# Adafruit_ESP32-S3_TFT_Feather.net
KiCad netlist of a schematic drawn in EAGLE
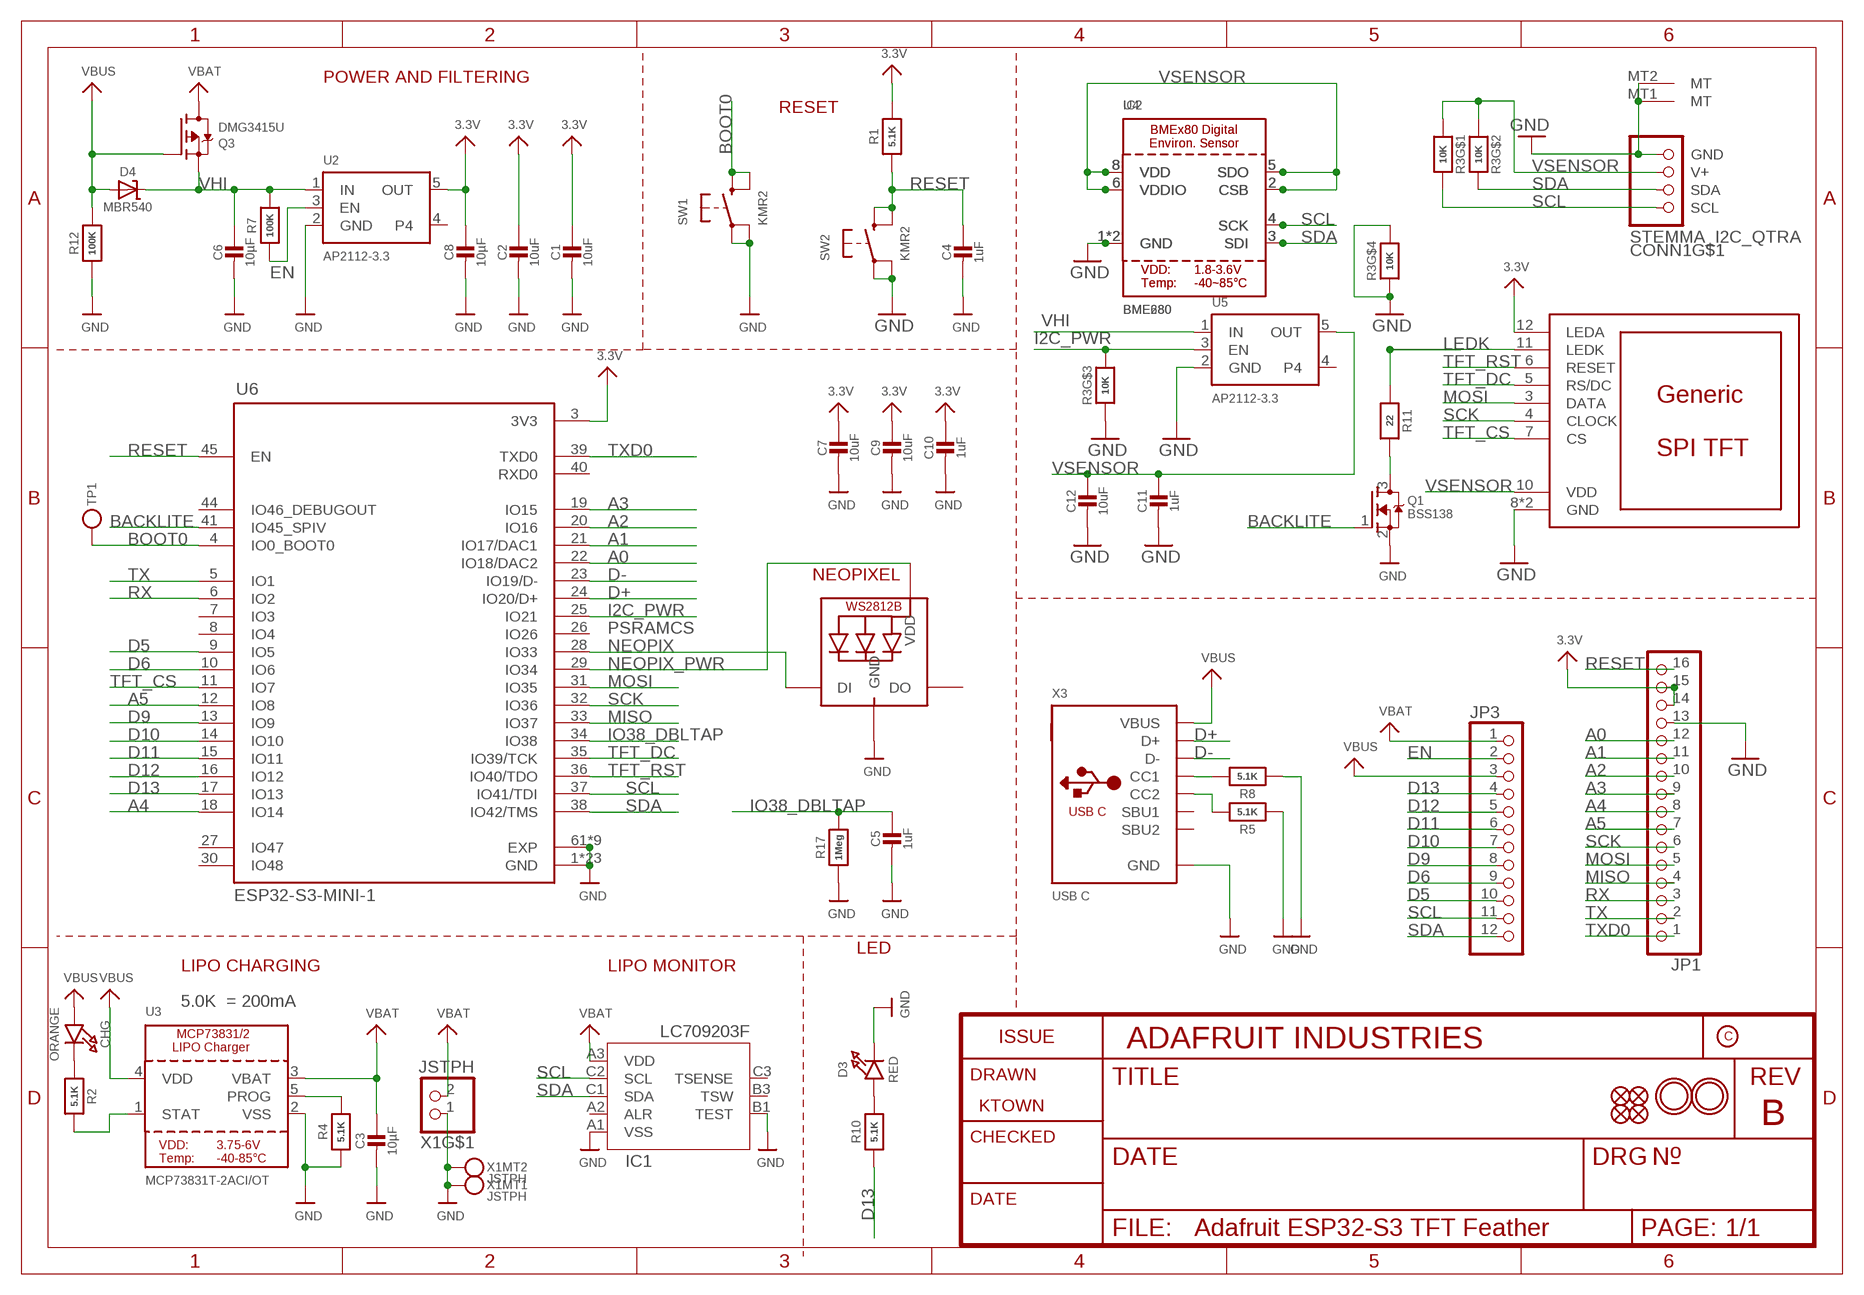
[diagram p0: schematic, sheet 1]

(export (version "E")
  (design (tool "Eeschema 10.0.6"))
  (components
    (comp (ref "C1")
      (value "10uF")
      (footprint "eagle-import:0805-NO")
      (libsource (lib "eagle-import") (part "CAP_CERAMIC0805-NOOUTLINE"))
    )
    (comp (ref "C2")
      (value "10uF")
      (footprint "eagle-import:0805-NO")
      (libsource (lib "eagle-import") (part "CAP_CERAMIC0805-NOOUTLINE"))
    )
    (comp (ref "C3")
      (value "10µF")
      (footprint "eagle-import:0805-NO")
      (libsource (lib "eagle-import") (part "CAP_CERAMIC0805-NOOUTLINE"))
    )
    (comp (ref "C4")
      (value "1uF")
      (footprint "eagle-import:0603-NO")
      (libsource (lib "eagle-import") (part "CAP_CERAMIC0603_NO"))
    )
    (comp (ref "C5")
      (value "1uF")
      (footprint "eagle-import:0603-NO")
      (libsource (lib "eagle-import") (part "CAP_CERAMIC0603_NO"))
    )
    (comp (ref "C6")
      (value "10µF")
      (footprint "eagle-import:0805-NO")
      (libsource (lib "eagle-import") (part "CAP_CERAMIC0805-NOOUTLINE"))
    )
    (comp (ref "C7")
      (value "10uF")
      (footprint "eagle-import:0805-NO")
      (libsource (lib "eagle-import") (part "CAP_CERAMIC0805-NOOUTLINE"))
    )
    (comp (ref "C8")
      (value "10µF")
      (footprint "eagle-import:0805-NO")
      (fields (field (name "REV") "C"))
      (libsource (lib "eagle-import") (part "CAP_CERAMIC0805-NOOUTLINE"))
    )
    (comp (ref "C9")
      (value "10uF")
      (footprint "eagle-import:0805-NO")
      (libsource (lib "eagle-import") (part "CAP_CERAMIC0805-NOOUTLINE"))
    )
    (comp (ref "C10")
      (value "1uF")
      (footprint "eagle-import:0603-NO")
      (libsource (lib "eagle-import") (part "CAP_CERAMIC0603_NO"))
    )
    (comp (ref "C11")
      (value "1uF")
      (footprint "eagle-import:0603-NO")
      (libsource (lib "eagle-import") (part "CAP_CERAMIC0603_NO"))
    )
    (comp (ref "C12")
      (value "10uF")
      (footprint "eagle-import:0805-NO")
      (libsource (lib "eagle-import") (part "CAP_CERAMIC0805-NOOUTLINE"))
    )
    (comp (ref "CHG")
      (value "ORANGE")
      (footprint "eagle-import:CHIPLED_0603_NOOUTLINE")
      (libsource (lib "eagle-import") (part "LED0603_NOOUTLINE"))
    )
    (comp (ref "CONN1")
      (value "STEMMA_I2C_QTRA")
      (footprint "eagle-import:JST_SH4_RA")
      (libsource (lib "eagle-import") (part "STEMMA_I2C_QTRA"))
    )
    (comp (ref "D3")
      (value "RED")
      (footprint "eagle-import:CHIPLED_0603_NOOUTLINE")
      (libsource (lib "eagle-import") (part "LED0603_NOOUTLINE"))
    )
    (comp (ref "D4")
      (value "MBR540")
      (footprint "eagle-import:SOD-123")
      (libsource (lib "eagle-import") (part "DIODE-SCHOTTKYSOD-123"))
    )
    (comp (ref "DISP1")
      (value "DISP_LCD_GENERIC_SPI_1.14IN_240X135_WRAPUNDER")
      (footprint "eagle-import:TFT_1.14IN_240X135_WRAPUNDER")
      (libsource (lib "eagle-import") (part "DISP_LCD_GENERIC_SPI_1.14IN_240X135_WRAPUNDER"))
    )
    (comp (ref "IC1")
      (value "LC709203F/MH")
      (footprint "eagle-import:WLCSP9")
      (libsource (lib "eagle-import") (part "LC709203F/MH"))
    )
    (comp (ref "IC2")
      (value "BME680")
      (footprint "eagle-import:BME680")
      (libsource (lib "eagle-import") (part "BME680"))
    )
    (comp (ref "JP1")
      (value "HEADER-1X16_MIN")
      (footprint "eagle-import:1X16_ROUND_MIN")
      (libsource (lib "eagle-import") (part "HEADER-1X16_MIN"))
    )
    (comp (ref "JP3")
      (value "HEADER-1X12_MIN")
      (footprint "eagle-import:1X12_ROUND_MIN")
      (libsource (lib "eagle-import") (part "HEADER-1X12_MIN"))
    )
    (comp (ref "LED1")
      (value "WS2812B_SK6805_1515")
      (footprint "eagle-import:SK6805_1515")
      (libsource (lib "eagle-import") (part "WS2812B_SK6805_1515"))
    )
    (comp (ref "Q1")
      (value "BSS138")
      (footprint "eagle-import:SOT23-R")
      (libsource (lib "eagle-import") (part "MOSFET-NREFLOW"))
    )
    (comp (ref "Q3")
      (value "DMG3415U")
      (footprint "eagle-import:SOT23-R")
      (libsource (lib "eagle-import") (part "MOSFET-P"))
    )
    (comp (ref "R1")
      (value "5.1K")
      (footprint "eagle-import:0603-NO")
      (libsource (lib "eagle-import") (part "RESISTOR_0603_NOOUT"))
    )
    (comp (ref "R2")
      (value "5.1K")
      (footprint "eagle-import:0603-NO")
      (libsource (lib "eagle-import") (part "RESISTOR_0603_NOOUT"))
    )
    (comp (ref "R3")
      (value "10K")
      (footprint "eagle-import:RESPACK_4X0603")
      (libsource (lib "eagle-import") (part "RESISTOR_4PACK"))
    )
    (comp (ref "R4")
      (value "5.1K")
      (footprint "eagle-import:0603-NO")
      (libsource (lib "eagle-import") (part "RESISTOR_0603_NOOUT"))
    )
    (comp (ref "R5")
      (value "5.1K")
      (footprint "eagle-import:0603-NO")
      (libsource (lib "eagle-import") (part "RESISTOR_0603_NOOUT"))
    )
    (comp (ref "R7")
      (value "100K")
      (footprint "eagle-import:0603-NO")
      (libsource (lib "eagle-import") (part "RESISTOR_0603_NOOUT"))
    )
    (comp (ref "R8")
      (value "5.1K")
      (footprint "eagle-import:0603-NO")
      (libsource (lib "eagle-import") (part "RESISTOR_0603_NOOUT"))
    )
    (comp (ref "R10")
      (value "5.1K")
      (footprint "eagle-import:0603-NO")
      (libsource (lib "eagle-import") (part "RESISTOR_0603_NOOUT"))
    )
    (comp (ref "R11")
      (value "22")
      (footprint "eagle-import:0603-NO")
      (libsource (lib "eagle-import") (part "RESISTOR_0603_NOOUT"))
    )
    (comp (ref "R12")
      (value "100K")
      (footprint "eagle-import:0603-NO")
      (libsource (lib "eagle-import") (part "RESISTOR_0603_NOOUT"))
    )
    (comp (ref "R17")
      (value "1Meg")
      (footprint "eagle-import:0603-NO")
      (libsource (lib "eagle-import") (part "RESISTOR_0603_NOOUT"))
    )
    (comp (ref "SW1")
      (value "KMR2")
      (footprint "eagle-import:BTN_KMR2_4.6X2.8")
      (libsource (lib "eagle-import") (part "SWITCH_TACT_SMT4.6X2.8"))
    )
    (comp (ref "SW2")
      (value "KMR2")
      (footprint "eagle-import:BTN_KMR2_4.6X2.8")
      (libsource (lib "eagle-import") (part "SWITCH_TACT_SMT4.6X2.8"))
    )
    (comp (ref "TP1")
      (value "TESTPOINTROUND1.5MMNO")
      (footprint "eagle-import:TESTPOINT_ROUND_1.5MM_NO")
      (libsource (lib "eagle-import") (part "TESTPOINTROUND1.5MMNO"))
    )
    (comp (ref "U$31")
      (value "MOUNTINGHOLE2.5")
      (footprint "eagle-import:MOUNTINGHOLE_2.5_PLATED")
      (libsource (lib "eagle-import") (part "MOUNTINGHOLE2.5"))
    )
    (comp (ref "U$32")
      (value "MOUNTINGHOLE2.5")
      (footprint "eagle-import:MOUNTINGHOLE_2.5_PLATED")
      (libsource (lib "eagle-import") (part "MOUNTINGHOLE2.5"))
    )
    (comp (ref "U$34")
      (value "FIDUCIAL_1MM")
      (footprint "eagle-import:FIDUCIAL_1MM")
      (libsource (lib "eagle-import") (part "FIDUCIAL_1MM"))
    )
    (comp (ref "U$35")
      (value "FIDUCIAL_1MM")
      (footprint "eagle-import:FIDUCIAL_1MM")
      (libsource (lib "eagle-import") (part "FIDUCIAL_1MM"))
    )
    (comp (ref "U$55")
      (value "FIDUCIAL_1MM")
      (footprint "eagle-import:FIDUCIAL_1MM")
      (libsource (lib "eagle-import") (part "FIDUCIAL_1MM"))
    )
    (comp (ref "U$56")
      (value "FIDUCIAL_1MM")
      (footprint "eagle-import:FIDUCIAL_1MM")
      (libsource (lib "eagle-import") (part "FIDUCIAL_1MM"))
    )
    (comp (ref "U2")
      (value "AP2112-3.3")
      (footprint "eagle-import:SOT23-5")
      (libsource (lib "eagle-import") (part "VREG_SOT23-5"))
    )
    (comp (ref "U3")
      (value "MCP73831T-2ACI/OT")
      (footprint "eagle-import:SOT23-5")
      (libsource (lib "eagle-import") (part "MCP73831/2"))
    )
    (comp (ref "U4")
      (value "BME280")
      (footprint "eagle-import:BME280")
      (libsource (lib "eagle-import") (part "BME280"))
    )
    (comp (ref "U5")
      (value "AP2112-3.3")
      (footprint "eagle-import:SOT23-5")
      (libsource (lib "eagle-import") (part "VREG_SOT23-5"))
    )
    (comp (ref "U6")
      (value "ESP32-S3-MINI-1")
      (footprint "eagle-import:QFN60_ESP32-S2-MINI-1_EXP")
      (fields
        (field (name "MANUFACTURER_PART_NUMBER") "ESP32-S2-MINI-1")
        (field (name "COPYRIGHT") "Copyright (C) 2018 Accelerated Designs. All rights reserved")
      )
      (libsource (lib "eagle-import") (part "ESP32-S3-MINI-1"))
    )
    (comp (ref "X1")
      (value "JSTPH")
      (footprint "eagle-import:JSTPH2_BATT")
      (libsource (lib "eagle-import") (part "CON_JST_PH_2PIN_MT_BATT"))
    )
    (comp (ref "X3")
      (value "USB C")
      (footprint "eagle-import:USB_C_CUSB31-CFM2AX-01-X")
      (libsource (lib "eagle-import") (part "USB_C"))
    )
  )
  (nets
    (net (code "1") (name "/A0") (class "Default")
      (node (ref "JP1") (pin "12") (pinfunction "12_12") (pintype "passive"))
      (node (ref "U6") (pin "22") (pinfunction "IO18/DAC2_22") (pintype "bidirectional"))
    )
    (net (code "2") (name "/A1") (class "Default")
      (node (ref "JP1") (pin "11") (pinfunction "11_11") (pintype "passive"))
      (node (ref "U6") (pin "21") (pinfunction "IO17/DAC1_21") (pintype "bidirectional"))
    )
    (net (code "3") (name "/A2") (class "Default")
      (node (ref "JP1") (pin "10") (pinfunction "10_10") (pintype "passive"))
      (node (ref "U6") (pin "20") (pinfunction "IO16_20") (pintype "bidirectional"))
    )
    (net (code "4") (name "/A3") (class "Default")
      (node (ref "JP1") (pin "9") (pinfunction "9_9") (pintype "passive"))
      (node (ref "U6") (pin "19") (pinfunction "IO15_19") (pintype "bidirectional"))
    )
    (net (code "5") (name "/A4") (class "Default")
      (node (ref "JP1") (pin "8") (pinfunction "8_8") (pintype "passive"))
      (node (ref "U6") (pin "18") (pinfunction "IO14_18") (pintype "bidirectional"))
    )
    (net (code "6") (name "/A5") (class "Default")
      (node (ref "JP1") (pin "7") (pinfunction "7_7") (pintype "passive"))
      (node (ref "U6") (pin "12") (pinfunction "IO8_12") (pintype "bidirectional"))
    )
    (net (code "7") (name "/BACKLITE") (class "Default")
      (node (ref "Q1") (pin "1") (pinfunction "G_1") (pintype "bidirectional"))
      (node (ref "U6") (pin "41") (pinfunction "IO45_SPIV_41") (pintype "bidirectional"))
    )
    (net (code "8") (name "/BOOT0") (class "Default")
      (node (ref "SW1") (pin "B") (pinfunction "S_B") (pintype "passive"))
      (node (ref "SW1") (pin "B'") (pinfunction "S1_B'") (pintype "passive"))
      (node (ref "TP1") (pin "P$1") (pinfunction "P$1_P$1") (pintype "bidirectional"))
      (node (ref "U6") (pin "4") (pinfunction "IO0_BOOT0_4") (pintype "bidirectional"))
    )
    (net (code "9") (name "/D+") (class "Default")
      (node (ref "U6") (pin "24") (pinfunction "IO20/D+_24") (pintype "bidirectional"))
      (node (ref "X3") (pin "A6") (pinfunction "D+_A6") (pintype "bidirectional"))
      (node (ref "X3") (pin "B6") (pinfunction "D+_B6") (pintype "bidirectional"))
    )
    (net (code "10") (name "/D-") (class "Default")
      (node (ref "U6") (pin "23") (pinfunction "IO19/D-_23") (pintype "bidirectional"))
      (node (ref "X3") (pin "A7") (pinfunction "D-_A7") (pintype "bidirectional"))
      (node (ref "X3") (pin "B7") (pinfunction "D-_B7") (pintype "bidirectional"))
    )
    (net (code "11") (name "/D5") (class "Default")
      (node (ref "JP3") (pin "10") (pinfunction "10_10") (pintype "passive"))
      (node (ref "U6") (pin "9") (pinfunction "IO5_9") (pintype "bidirectional"))
    )
    (net (code "12") (name "/D6") (class "Default")
      (node (ref "JP3") (pin "9") (pinfunction "9_9") (pintype "passive"))
      (node (ref "U6") (pin "10") (pinfunction "IO6_10") (pintype "bidirectional"))
    )
    (net (code "13") (name "/D9") (class "Default")
      (node (ref "JP3") (pin "8") (pinfunction "8_8") (pintype "passive"))
      (node (ref "U6") (pin "13") (pinfunction "IO9_13") (pintype "bidirectional"))
    )
    (net (code "14") (name "/D10") (class "Default")
      (node (ref "JP3") (pin "7") (pinfunction "7_7") (pintype "passive"))
      (node (ref "U6") (pin "14") (pinfunction "IO10_14") (pintype "bidirectional"))
    )
    (net (code "15") (name "/D11") (class "Default")
      (node (ref "JP3") (pin "6") (pinfunction "6_6") (pintype "passive"))
      (node (ref "U6") (pin "15") (pinfunction "IO11_15") (pintype "bidirectional"))
    )
    (net (code "16") (name "/D12") (class "Default")
      (node (ref "JP3") (pin "5") (pinfunction "5_5") (pintype "passive"))
      (node (ref "U6") (pin "16") (pinfunction "IO12_16") (pintype "bidirectional"))
    )
    (net (code "17") (name "/D13") (class "Default")
      (node (ref "JP3") (pin "4") (pinfunction "4_4") (pintype "passive"))
      (node (ref "R10") (pin "1") (pinfunction "1_1") (pintype "passive"))
      (node (ref "U6") (pin "17") (pinfunction "IO13_17") (pintype "bidirectional"))
    )
    (net (code "18") (name "/EN") (class "Default")
      (node (ref "JP3") (pin "2") (pinfunction "2_2") (pintype "passive"))
      (node (ref "R7") (pin "1") (pinfunction "1_1") (pintype "passive"))
      (node (ref "U2") (pin "3") (pinfunction "EN_3") (pintype "input"))
    )
    (net (code "19") (name "/I2C_PWR") (class "Default")
      (node (ref "R3") (pin "6") (pinfunction "2_6") (pintype "passive"))
      (node (ref "U5") (pin "3") (pinfunction "EN_3") (pintype "input"))
      (node (ref "U6") (pin "25") (pinfunction "IO21_25") (pintype "bidirectional"))
    )
    (net (code "20") (name "/IO38_DBLTAP") (class "Default")
      (node (ref "C5") (pin "1") (pinfunction "1_1") (pintype "passive"))
      (node (ref "R17") (pin "2") (pinfunction "2_2") (pintype "passive"))
      (node (ref "U6") (pin "34") (pinfunction "IO38_34") (pintype "bidirectional"))
    )
    (net (code "21") (name "/LEDK") (class "Default")
      (node (ref "DISP1") (pin "11") (pinfunction "LEDK_11") (pintype "input"))
      (node (ref "R11") (pin "1") (pinfunction "1_1") (pintype "passive"))
    )
    (net (code "22") (name "/MISO") (class "Default")
      (node (ref "JP1") (pin "4") (pinfunction "4_4") (pintype "passive"))
      (node (ref "U6") (pin "33") (pinfunction "IO37_33") (pintype "bidirectional"))
    )
    (net (code "23") (name "/MOSI") (class "Default")
      (node (ref "DISP1") (pin "3") (pinfunction "DATA_3") (pintype "bidirectional"))
      (node (ref "JP1") (pin "5") (pinfunction "5_5") (pintype "passive"))
      (node (ref "U6") (pin "31") (pinfunction "IO35_31") (pintype "input"))
    )
    (net (code "24") (name "/NEOPIX") (class "Default")
      (node (ref "LED1") (pin "1") (pinfunction "DI_1") (pintype "input"))
      (node (ref "U6") (pin "28") (pinfunction "IO33_28") (pintype "bidirectional"))
    )
    (net (code "25") (name "/NEOPIX_PWR") (class "Default")
      (node (ref "LED1") (pin "2") (pinfunction "VDD_2") (pintype "power_in"))
      (node (ref "U6") (pin "29") (pinfunction "IO34_29") (pintype "input"))
    )
    (net (code "26") (name "/RESET") (class "Default")
      (node (ref "C4") (pin "1") (pinfunction "1_1") (pintype "passive"))
      (node (ref "JP1") (pin "16") (pinfunction "16_16") (pintype "passive"))
      (node (ref "R1") (pin "1") (pinfunction "1_1") (pintype "passive"))
      (node (ref "SW2") (pin "B") (pinfunction "S_B") (pintype "passive"))
      (node (ref "SW2") (pin "B'") (pinfunction "S1_B'") (pintype "passive"))
      (node (ref "U6") (pin "45") (pinfunction "EN_45") (pintype "input"))
    )
    (net (code "27") (name "/RX") (class "Default")
      (node (ref "JP1") (pin "3") (pinfunction "3_3") (pintype "passive"))
      (node (ref "U6") (pin "6") (pinfunction "IO2_6") (pintype "bidirectional"))
    )
    (net (code "28") (name "/SCK") (class "Default")
      (node (ref "DISP1") (pin "4") (pinfunction "CLOCK_4") (pintype "input"))
      (node (ref "JP1") (pin "6") (pinfunction "6_6") (pintype "passive"))
      (node (ref "U6") (pin "32") (pinfunction "IO36_32") (pintype "bidirectional"))
    )
    (net (code "29") (name "/SCL") (class "Default")
      (node (ref "CONN1") (pin "4") (pinfunction "SCL_4") (pintype "passive"))
      (node (ref "IC1") (pin "C2") (pinfunction "SCL_C2") (pintype "bidirectional"))
      (node (ref "IC2") (pin "4") (pinfunction "SCK_4") (pintype "input"))
      (node (ref "JP3") (pin "11") (pinfunction "11_11") (pintype "passive"))
      (node (ref "R3") (pin "8") (pinfunction "2_8") (pintype "passive"))
      (node (ref "U4") (pin "4") (pinfunction "SCK_4") (pintype "input"))
      (node (ref "U6") (pin "37") (pinfunction "IO41/TDI_37") (pintype "bidirectional"))
    )
    (net (code "30") (name "/SDA") (class "Default")
      (node (ref "CONN1") (pin "3") (pinfunction "SDA_3") (pintype "passive"))
      (node (ref "IC1") (pin "C1") (pinfunction "SDA_C1") (pintype "bidirectional"))
      (node (ref "IC2") (pin "3") (pinfunction "SDI_3") (pintype "input"))
      (node (ref "JP3") (pin "12") (pinfunction "12_12") (pintype "passive"))
      (node (ref "R3") (pin "7") (pinfunction "2_7") (pintype "passive"))
      (node (ref "U4") (pin "3") (pinfunction "SDI_3") (pintype "input"))
      (node (ref "U6") (pin "38") (pinfunction "IO42/TMS_38") (pintype "bidirectional"))
    )
    (net (code "31") (name "/TFT_CS") (class "Default")
      (node (ref "DISP1") (pin "7") (pinfunction "CS_7") (pintype "input"))
      (node (ref "U6") (pin "11") (pinfunction "IO7_11") (pintype "bidirectional"))
    )
    (net (code "32") (name "/TFT_DC") (class "Default")
      (node (ref "DISP1") (pin "5") (pinfunction "RS/DC_5") (pintype "input"))
      (node (ref "U6") (pin "35") (pinfunction "IO39/TCK_35") (pintype "bidirectional"))
    )
    (net (code "33") (name "/TFT_RST") (class "Default")
      (node (ref "DISP1") (pin "6") (pinfunction "RESET_6") (pintype "input"))
      (node (ref "U6") (pin "36") (pinfunction "IO40/TDO_36") (pintype "bidirectional"))
    )
    (net (code "34") (name "/TX") (class "Default")
      (node (ref "JP1") (pin "2") (pinfunction "2_2") (pintype "passive"))
      (node (ref "U6") (pin "5") (pinfunction "IO1_5") (pintype "bidirectional"))
    )
    (net (code "35") (name "/TXD0") (class "Default")
      (node (ref "JP1") (pin "1") (pinfunction "1_1") (pintype "passive"))
      (node (ref "U6") (pin "39") (pinfunction "TXD0_39") (pintype "bidirectional"))
    )
    (net (code "36") (name "/VHI") (class "Default")
      (node (ref "C6") (pin "1") (pinfunction "1_1") (pintype "passive"))
      (node (ref "D4") (pin "C") (pinfunction "C_C") (pintype "passive"))
      (node (ref "Q3") (pin "2") (pinfunction "S_2") (pintype "passive"))
      (node (ref "R7") (pin "2") (pinfunction "2_2") (pintype "passive"))
      (node (ref "U2") (pin "1") (pinfunction "IN_1") (pintype "power_in"))
      (node (ref "U5") (pin "1") (pinfunction "IN_1") (pintype "power_in"))
    )
    (net (code "37") (name "/VSENSOR") (class "Default")
      (node (ref "C11") (pin "1") (pinfunction "1_1") (pintype "passive"))
      (node (ref "C12") (pin "1") (pinfunction "1_1") (pintype "passive"))
      (node (ref "CONN1") (pin "2") (pinfunction "V+_2") (pintype "passive"))
      (node (ref "DISP1") (pin "10") (pinfunction "VDD_10") (pintype "power_in"))
      (node (ref "IC2") (pin "2") (pinfunction "CSB_2") (pintype "input"))
      (node (ref "IC2") (pin "5") (pinfunction "SDO_5") (pintype "output"))
      (node (ref "IC2") (pin "6") (pinfunction "VDDIO_6") (pintype "power_in"))
      (node (ref "IC2") (pin "8") (pinfunction "VDD_8") (pintype "power_in"))
      (node (ref "R3") (pin "1") (pinfunction "1_1") (pintype "passive"))
      (node (ref "R3") (pin "2") (pinfunction "1_2") (pintype "passive"))
      (node (ref "U4") (pin "2") (pinfunction "CSB_2") (pintype "input"))
      (node (ref "U4") (pin "5") (pinfunction "SDO_5") (pintype "output"))
      (node (ref "U4") (pin "6") (pinfunction "VDDIO_6") (pintype "power_in"))
      (node (ref "U4") (pin "8") (pinfunction "VDD_8") (pintype "power_in"))
      (node (ref "U5") (pin "5") (pinfunction "OUT_5") (pintype "power_in"))
    )
    (net (code "38") (name "3.3V") (class "Default")
      (node (ref "C1") (pin "1") (pinfunction "1_1") (pintype "passive"))
      (node (ref "C10") (pin "1") (pinfunction "1_1") (pintype "passive"))
      (node (ref "C2") (pin "1") (pinfunction "1_1") (pintype "passive"))
      (node (ref "C7") (pin "1") (pinfunction "1_1") (pintype "passive"))
      (node (ref "C8") (pin "1") (pinfunction "1_1") (pintype "passive"))
      (node (ref "C9") (pin "1") (pinfunction "1_1") (pintype "passive"))
      (node (ref "DISP1") (pin "12") (pinfunction "LEDA_12") (pintype "input"))
      (node (ref "JP1") (pin "14") (pinfunction "14_14") (pintype "passive"))
      (node (ref "JP1") (pin "15") (pinfunction "15_15") (pintype "passive"))
      (node (ref "R1") (pin "2") (pinfunction "2_2") (pintype "passive"))
      (node (ref "U2") (pin "5") (pinfunction "OUT_5") (pintype "power_in"))
      (node (ref "U6") (pin "3") (pinfunction "3V3_3") (pintype "power_in"))
    )
    (net (code "39") (name "GND") (class "Default")
      (node (ref "C1") (pin "2") (pinfunction "2_2") (pintype "passive"))
      (node (ref "C10") (pin "2") (pinfunction "2_2") (pintype "passive"))
      (node (ref "C11") (pin "2") (pinfunction "2_2") (pintype "passive"))
      (node (ref "C12") (pin "2") (pinfunction "2_2") (pintype "passive"))
      (node (ref "C2") (pin "2") (pinfunction "2_2") (pintype "passive"))
      (node (ref "C3") (pin "2") (pinfunction "2_2") (pintype "passive"))
      (node (ref "C4") (pin "2") (pinfunction "2_2") (pintype "passive"))
      (node (ref "C5") (pin "2") (pinfunction "2_2") (pintype "passive"))
      (node (ref "C6") (pin "2") (pinfunction "2_2") (pintype "passive"))
      (node (ref "C7") (pin "2") (pinfunction "2_2") (pintype "passive"))
      (node (ref "C8") (pin "2") (pinfunction "2_2") (pintype "passive"))
      (node (ref "C9") (pin "2") (pinfunction "2_2") (pintype "passive"))
      (node (ref "CONN1") (pin "1") (pinfunction "GND_1") (pintype "passive"))
      (node (ref "CONN1") (pin "MT1") (pinfunction "MT_MT1") (pintype "bidirectional"))
      (node (ref "CONN1") (pin "MT2") (pinfunction "MT_MT2") (pintype "bidirectional"))
      (node (ref "D3") (pin "C") (pinfunction "C_C") (pintype "passive"))
      (node (ref "DISP1") (pin "13") (pinfunction "GND_13") (pintype "power_in"))
      (node (ref "DISP1") (pin "8") (pinfunction "GND_8") (pintype "power_in"))
      (node (ref "IC1") (pin "A1") (pinfunction "VSS_A1") (pintype "power_in"))
      (node (ref "IC1") (pin "B1") (pinfunction "TEST_B1") (pintype "input"))
      (node (ref "IC2") (pin "1") (pinfunction "GND_1") (pintype "power_in"))
      (node (ref "IC2") (pin "7") (pinfunction "GND_7") (pintype "power_in"))
      (node (ref "JP1") (pin "13") (pinfunction "13_13") (pintype "passive"))
      (node (ref "LED1") (pin "4") (pinfunction "GND_4") (pintype "power_in"))
      (node (ref "Q1") (pin "2") (pinfunction "S_2") (pintype "bidirectional"))
      (node (ref "R12") (pin "1") (pinfunction "1_1") (pintype "passive"))
      (node (ref "R17") (pin "1") (pinfunction "1_1") (pintype "passive"))
      (node (ref "R3") (pin "3") (pinfunction "1_3") (pintype "passive"))
      (node (ref "R3") (pin "4") (pinfunction "1_4") (pintype "passive"))
      (node (ref "R3") (pin "5") (pinfunction "2_5") (pintype "passive"))
      (node (ref "R4") (pin "1") (pinfunction "1_1") (pintype "passive"))
      (node (ref "R5") (pin "1") (pinfunction "1_1") (pintype "passive"))
      (node (ref "R8") (pin "1") (pinfunction "1_1") (pintype "passive"))
      (node (ref "SW1") (pin "A") (pinfunction "P_A") (pintype "passive"))
      (node (ref "SW1") (pin "A'") (pinfunction "P1_A'") (pintype "passive"))
      (node (ref "SW2") (pin "A") (pinfunction "P_A") (pintype "passive"))
      (node (ref "SW2") (pin "A'") (pinfunction "P1_A'") (pintype "passive"))
      (node (ref "U2") (pin "2") (pinfunction "GND_2") (pintype "power_in"))
      (node (ref "U3") (pin "2") (pinfunction "VSS_2") (pintype "power_in"))
      (node (ref "U4") (pin "1") (pinfunction "GND_1") (pintype "power_in"))
      (node (ref "U4") (pin "7") (pinfunction "GND_7") (pintype "power_in"))
      (node (ref "U5") (pin "2") (pinfunction "GND_2") (pintype "power_in"))
      (node (ref "U6") (pin "1") (pinfunction "GND_1") (pintype "power_in"))
      (node (ref "U6") (pin "2") (pinfunction "GND_2") (pintype "power_in"))
      (node (ref "U6") (pin "42") (pinfunction "GND_42") (pintype "power_in"))
      (node (ref "U6") (pin "43") (pinfunction "GND_43") (pintype "power_in"))
      (node (ref "U6") (pin "46") (pinfunction "GND_46") (pintype "power_in"))
      (node (ref "U6") (pin "47") (pinfunction "GND_47") (pintype "power_in"))
      (node (ref "U6") (pin "48") (pinfunction "GND_48") (pintype "power_in"))
      (node (ref "U6") (pin "49") (pinfunction "GND_49") (pintype "power_in"))
      (node (ref "U6") (pin "50") (pinfunction "GND_50") (pintype "power_in"))
      (node (ref "U6") (pin "51") (pinfunction "GND_51") (pintype "power_in"))
      (node (ref "U6") (pin "52") (pinfunction "GND_52") (pintype "power_in"))
      (node (ref "U6") (pin "53") (pinfunction "GND_53") (pintype "power_in"))
      (node (ref "U6") (pin "54") (pinfunction "GND_54") (pintype "power_in"))
      (node (ref "U6") (pin "55") (pinfunction "GND_55") (pintype "power_in"))
      (node (ref "U6") (pin "56") (pinfunction "GND_56") (pintype "power_in"))
      (node (ref "U6") (pin "57") (pinfunction "GND_57") (pintype "power_in"))
      (node (ref "U6") (pin "58") (pinfunction "GND_58") (pintype "power_in"))
      (node (ref "U6") (pin "59") (pinfunction "GND_59") (pintype "power_in"))
      (node (ref "U6") (pin "60") (pinfunction "GND_60") (pintype "power_in"))
      (node (ref "U6") (pin "61") (pinfunction "EXP_61") (pintype "power_in"))
      (node (ref "U6") (pin "62") (pinfunction "GND_62") (pintype "power_in"))
      (node (ref "U6") (pin "63") (pinfunction "GND_63") (pintype "power_in"))
      (node (ref "U6") (pin "64") (pinfunction "GND_64") (pintype "power_in"))
      (node (ref "U6") (pin "65") (pinfunction "GND_65") (pintype "power_in"))
      (node (ref "U6") (pin "66") (pinfunction "EXP_66") (pintype "power_in"))
      (node (ref "U6") (pin "67") (pinfunction "EXP_67") (pintype "power_in"))
      (node (ref "U6") (pin "68") (pinfunction "EXP_68") (pintype "power_in"))
      (node (ref "U6") (pin "69") (pinfunction "EXP_69") (pintype "power_in"))
      (node (ref "U6") (pin "70") (pinfunction "EXP_70") (pintype "power_in"))
      (node (ref "U6") (pin "71") (pinfunction "EXP_71") (pintype "power_in"))
      (node (ref "U6") (pin "72") (pinfunction "EXP_72") (pintype "power_in"))
      (node (ref "U6") (pin "73") (pinfunction "EXP_73") (pintype "power_in"))
      (node (ref "X1") (pin "1") (pinfunction "1_1") (pintype "passive"))
      (node (ref "X1") (pin "NC1") (pinfunction "P$1_NC1") (pintype "bidirectional"))
      (node (ref "X1") (pin "NC2") (pinfunction "P$1_NC2") (pintype "bidirectional"))
      (node (ref "X3") (pin "A1B12") (pinfunction "GND_A1B12") (pintype "power_in"))
      (node (ref "X3") (pin "B1A12") (pinfunction "GND_B1A12") (pintype "power_in"))
    )
    (net (code "40") (name "Net-(CHG-PadC)") (class "Default")
      (node (ref "CHG") (pin "C") (pinfunction "C_C") (pintype "passive"))
      (node (ref "R2") (pin "1") (pinfunction "1_1") (pintype "passive"))
    )
    (net (code "41") (name "Net-(D3-PadA)") (class "Default")
      (node (ref "D3") (pin "A") (pinfunction "A_A") (pintype "passive"))
      (node (ref "R10") (pin "2") (pinfunction "2_2") (pintype "passive"))
    )
    (net (code "42") (name "Net-(Q1-D)") (class "Default")
      (node (ref "Q1") (pin "3") (pinfunction "D_3") (pintype "bidirectional"))
      (node (ref "R11") (pin "2") (pinfunction "2_2") (pintype "passive"))
    )
    (net (code "43") (name "Net-(U3-PROG)") (class "Default")
      (node (ref "R4") (pin "2") (pinfunction "2_2") (pintype "passive"))
      (node (ref "U3") (pin "5") (pinfunction "PROG_5") (pintype "input"))
    )
    (net (code "44") (name "Net-(U3-STAT)") (class "Default")
      (node (ref "R2") (pin "2") (pinfunction "2_2") (pintype "passive"))
      (node (ref "U3") (pin "1") (pinfunction "STAT_1") (pintype "output"))
    )
    (net (code "45") (name "Net-(X3-CC1)") (class "Default")
      (node (ref "R8") (pin "2") (pinfunction "2_2") (pintype "passive"))
      (node (ref "X3") (pin "A5") (pinfunction "CC1_A5") (pintype "bidirectional"))
    )
    (net (code "46") (name "Net-(X3-CC2)") (class "Default")
      (node (ref "R5") (pin "2") (pinfunction "2_2") (pintype "passive"))
      (node (ref "X3") (pin "B5") (pinfunction "CC2_B5") (pintype "bidirectional"))
    )
    (net (code "47") (name "VBAT") (class "Default")
      (node (ref "C3") (pin "1") (pinfunction "1_1") (pintype "passive"))
      (node (ref "IC1") (pin "A3") (pinfunction "VDD_A3") (pintype "power_in"))
      (node (ref "JP3") (pin "1") (pinfunction "1_1") (pintype "passive"))
      (node (ref "Q3") (pin "3") (pinfunction "D_3") (pintype "passive"))
      (node (ref "U3") (pin "3") (pinfunction "VBAT_3") (pintype "power_in"))
      (node (ref "X1") (pin "2") (pinfunction "2_2") (pintype "passive"))
    )
    (net (code "48") (name "VBUS") (class "Default")
      (node (ref "CHG") (pin "A") (pinfunction "A_A") (pintype "passive"))
      (node (ref "D4") (pin "A") (pinfunction "A_A") (pintype "passive"))
      (node (ref "JP3") (pin "3") (pinfunction "3_3") (pintype "passive"))
      (node (ref "Q3") (pin "1") (pinfunction "G_1") (pintype "passive"))
      (node (ref "R12") (pin "2") (pinfunction "2_2") (pintype "passive"))
      (node (ref "U3") (pin "4") (pinfunction "VDD_4") (pintype "power_in"))
      (node (ref "X3") (pin "A4B9") (pinfunction "VBUS_A4B9") (pintype "power_in"))
      (node (ref "X3") (pin "B4A9") (pinfunction "VBUS_B4A9") (pintype "power_in"))
    )
    (net (code "49") (name "unconnected-(IC1-ALR-PadA2)") (class "Default")
      (node (ref "IC1") (pin "A2") (pinfunction "ALR_A2") (pintype "output"))
    )
    (net (code "50") (name "unconnected-(IC1-TSENSE-PadC3)") (class "Default")
      (node (ref "IC1") (pin "C3") (pinfunction "TSENSE_C3") (pintype "passive"))
    )
    (net (code "51") (name "unconnected-(IC1-TSW-PadB3)") (class "Default")
      (node (ref "IC1") (pin "B3") (pinfunction "TSW_B3") (pintype "output"))
    )
    (net (code "52") (name "unconnected-(LED1-DO-Pad3)") (class "Default")
      (node (ref "LED1") (pin "3") (pinfunction "DO_3") (pintype "output"))
    )
    (net (code "53") (name "unconnected-(U2-P4-Pad4)") (class "Default")
      (node (ref "U2") (pin "4") (pinfunction "P4_4") (pintype "bidirectional"))
    )
    (net (code "54") (name "unconnected-(U5-P4-Pad4)") (class "Default")
      (node (ref "U5") (pin "4") (pinfunction "P4_4") (pintype "bidirectional"))
    )
    (net (code "55") (name "unconnected-(U6-IO3-Pad7)") (class "Default")
      (node (ref "U6") (pin "7") (pinfunction "IO3_7") (pintype "bidirectional"))
    )
    (net (code "56") (name "unconnected-(U6-IO4-Pad8)") (class "Default")
      (node (ref "U6") (pin "8") (pinfunction "IO4_8") (pintype "bidirectional"))
    )
    (net (code "57") (name "unconnected-(U6-IO26-Pad26)") (class "Default")
      (node (ref "U6") (pin "26") (pinfunction "IO26_26") (pintype "bidirectional"))
    )
    (net (code "58") (name "unconnected-(U6-IO46_DEBUGOUT-Pad44)") (class "Default")
      (node (ref "U6") (pin "44") (pinfunction "IO46_DEBUGOUT_44") (pintype "input"))
    )
    (net (code "59") (name "unconnected-(U6-IO47-Pad27)") (class "Default")
      (node (ref "U6") (pin "27") (pinfunction "IO47_27") (pintype "bidirectional"))
    )
    (net (code "60") (name "unconnected-(U6-IO48-Pad30)") (class "Default")
      (node (ref "U6") (pin "30") (pinfunction "IO48_30") (pintype "bidirectional"))
    )
    (net (code "61") (name "unconnected-(U6-RXD0-Pad40)") (class "Default")
      (node (ref "U6") (pin "40") (pinfunction "RXD0_40") (pintype "bidirectional"))
    )
    (net (code "62") (name "unconnected-(X3-SBU1-PadA8)") (class "Default")
      (node (ref "X3") (pin "A8") (pinfunction "SBU1_A8") (pintype "bidirectional"))
    )
    (net (code "63") (name "unconnected-(X3-SBU2-PadB8)") (class "Default")
      (node (ref "X3") (pin "B8") (pinfunction "SBU2_B8") (pintype "bidirectional"))
    )
  )
)
